# Sheet3.net
KiCad netlist of a schematic drawn in Altium Designer
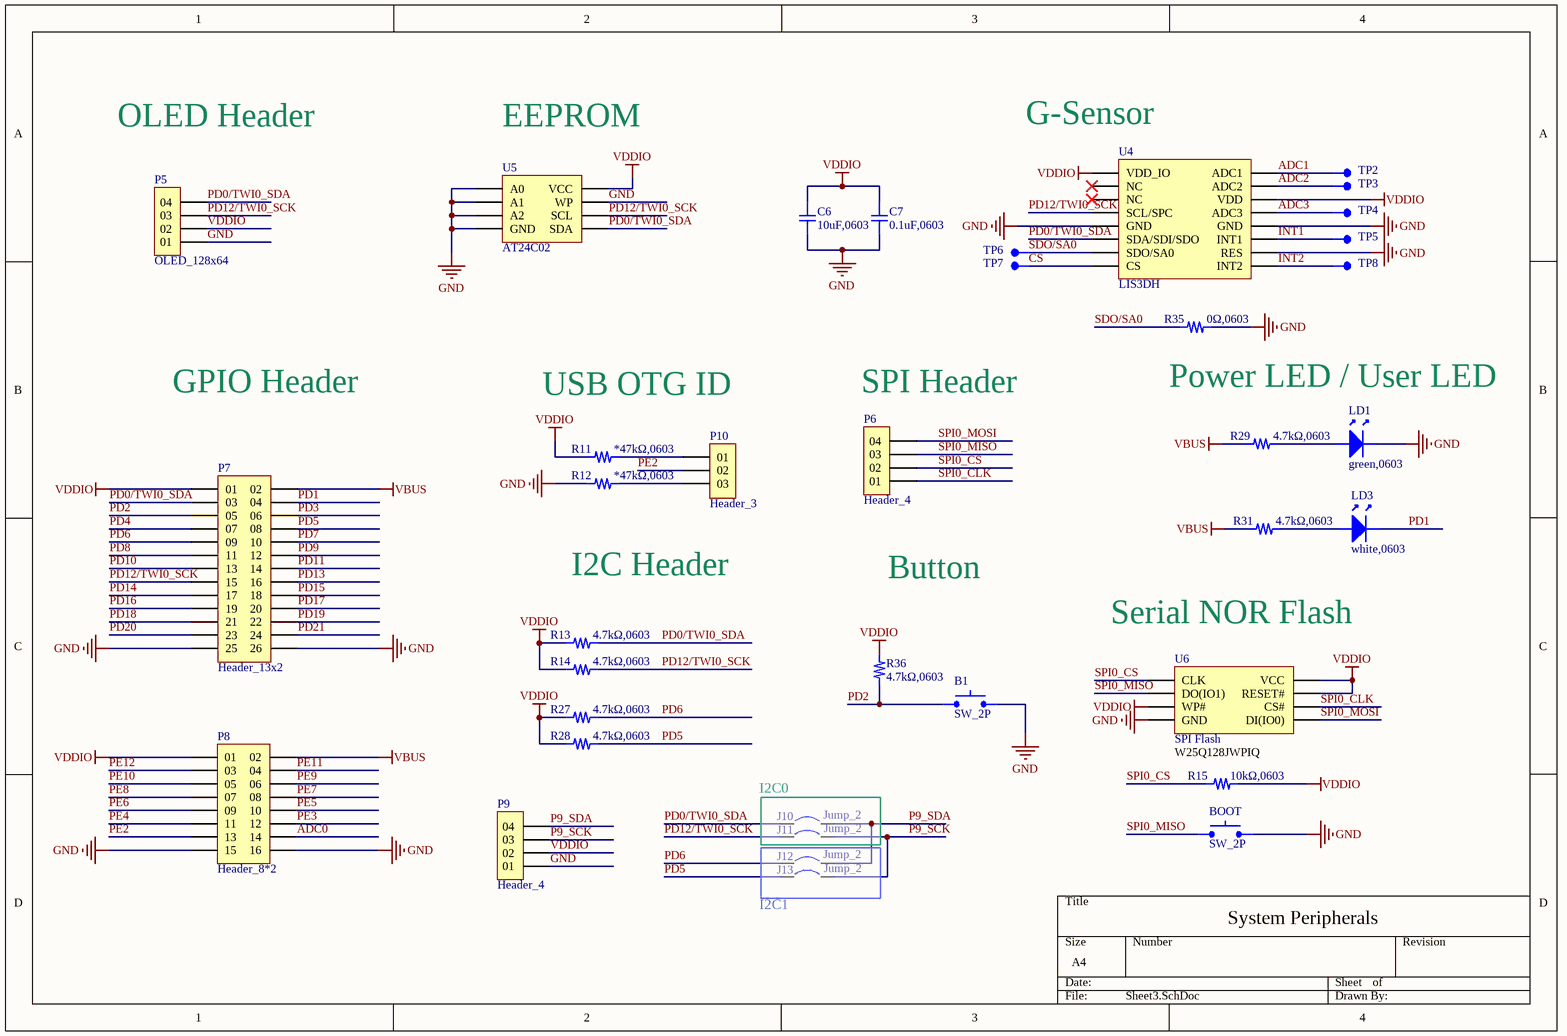
[diagram p0: Sheet3.SchDoc]

(export (version "E")
  (design (tool "Eeschema 10.0.6"))
  (components
    (comp (ref "B1") (value "SW_2P") (footprint "SW_2P_4") (libsource (lib "myLib1") (part "SW_2P")))
    (comp (ref "BOOT") (value "SW_2P") (footprint "SW_2P_4") (libsource (lib "myLib1") (part "SW_2P")))
    (comp (ref "C6") (value "10uF,0603") (footprint "C0603") (libsource (lib "myLib1") (part "Cap")))
    (comp (ref "C7") (value "0.1uF,0603") (footprint "C0603") (libsource (lib "myLib1") (part "Cap")))
    (comp (ref "J10") (value "Jump_2") (footprint "Jp_small") (libsource (lib "myLib1") (part "Jump_2")))
    (comp (ref "J11") (value "Jump_2") (footprint "Jp_small") (libsource (lib "myLib1") (part "Jump_2")))
    (comp (ref "J12") (value "Jump_2") (footprint "Jp_small") (libsource (lib "myLib1") (part "Jump_2")))
    (comp (ref "J13") (value "Jump_2") (footprint "Jp_small") (libsource (lib "myLib1") (part "Jump_2")))
    (comp (ref "LD1")
      (value "green,0603")
      (footprint "LED0603")
      (libsource (lib "myLib1") (part "Diode - LED"))
    )
    (comp (ref "LD3")
      (value "white,0603")
      (footprint "LED0603")
      (libsource (lib "myLib1") (part "Diode - LED"))
    )
    (comp (ref "P5")
      (value "OLED_128x64")
      (footprint "Header_4")
      (libsource (lib "myLib1") (part "Header_4"))
    )
    (comp (ref "P6")
      (value "Header_4")
      (footprint "HEADER_4_SMD")
      (libsource (lib "myLib1") (part "Header_4"))
    )
    (comp (ref "P7")
      (value "Header_13x2")
      (footprint "Header_13x2")
      (libsource (lib "myLib1") (part "Header_13x2"))
    )
    (comp (ref "P8")
      (value "Header_8*2")
      (footprint "Header_8*2")
      (libsource (lib "myLib1") (part "Header_8*2"))
    )
    (comp (ref "P9") (value "Header_4") (footprint "Header_4") (libsource (lib "myLib1") (part "Header_4")))
    (comp (ref "P10")
      (value "Header_3")
      (footprint "Header_3_2mm")
      (libsource (lib "myLib1") (part "Header_3"))
    )
    (comp (ref "R11") (value "*47kΩ,0603") (footprint "R0603") (libsource (lib "myLib1") (part "Res")))
    (comp (ref "R12") (value "*47kΩ,0603") (footprint "R0603") (libsource (lib "myLib1") (part "Res")))
    (comp (ref "R13") (value "4.7kΩ,0603") (footprint "R0603") (libsource (lib "myLib1") (part "Res")))
    (comp (ref "R14") (value "4.7kΩ,0603") (footprint "R0603") (libsource (lib "myLib1") (part "Res")))
    (comp (ref "R15") (value "10kΩ,0603") (footprint "R0603") (libsource (lib "myLib1") (part "Res")))
    (comp (ref "R27") (value "4.7kΩ,0603") (footprint "R0603") (libsource (lib "myLib1") (part "Res")))
    (comp (ref "R28") (value "4.7kΩ,0603") (footprint "R0603") (libsource (lib "myLib1") (part "Res")))
    (comp (ref "R29") (value "4.7kΩ,0603") (footprint "R0603") (libsource (lib "myLib1") (part "Res")))
    (comp (ref "R31") (value "4.7kΩ,0603") (footprint "R0603") (libsource (lib "myLib1") (part "Res")))
    (comp (ref "R35") (value "0Ω,0603") (footprint "R0603") (libsource (lib "myLib1") (part "Res")))
    (comp (ref "R36") (value "4.7kΩ,0603") (footprint "R0603") (libsource (lib "myLib1") (part "Res")))
    (comp (ref "TP2") (value "TP") (footprint "TP") (libsource (lib "myLib1") (part "TP")))
    (comp (ref "TP3") (value "TP") (footprint "TP") (libsource (lib "myLib1") (part "TP")))
    (comp (ref "TP4") (value "TP") (footprint "TP") (libsource (lib "myLib1") (part "TP")))
    (comp (ref "TP5") (value "TP") (footprint "TP") (libsource (lib "myLib1") (part "TP")))
    (comp (ref "TP6") (value "TP") (footprint "TP") (libsource (lib "myLib1") (part "TP")))
    (comp (ref "TP7") (value "TP") (footprint "TP") (libsource (lib "myLib1") (part "TP")))
    (comp (ref "TP8") (value "TP") (footprint "TP") (libsource (lib "myLib1") (part "TP")))
    (comp (ref "U4") (value "LIS3DH") (footprint "LGA-16") (libsource (lib "myLib1") (part "LIS3DH")))
    (comp (ref "U5") (value "AT24C02") (footprint "SOP8") (libsource (lib "myLib1") (part "AT24C02")))
    (comp (ref "U6") (value "SPI Flash") (footprint "WSON8") (libsource (lib "myLib1") (part "SPI Flash")))
  )
  (nets
    (net (code "1") (name "/ADC0") (class "Default")
      (node (ref "P8") (pin "14") (pinfunction "14_14") (pintype "passive"))
    )
    (net (code "2") (name "/ADC1") (class "Default")
      (node (ref "TP2") (pin "01") (pintype "passive"))
      (node (ref "U4") (pin "16") (pinfunction "ADC1_16") (pintype "passive"))
    )
    (net (code "3") (name "/ADC2") (class "Default")
      (node (ref "TP3") (pin "01") (pintype "passive"))
      (node (ref "U4") (pin "15") (pinfunction "ADC2_15") (pintype "passive"))
    )
    (net (code "4") (name "/ADC3") (class "Default")
      (node (ref "TP4") (pin "01") (pintype "passive"))
      (node (ref "U4") (pin "13") (pinfunction "ADC3_13") (pintype "passive"))
    )
    (net (code "5") (name "/CS") (class "Default")
      (node (ref "TP7") (pin "01") (pintype "passive"))
      (node (ref "U4") (pin "08") (pinfunction "CS_08") (pintype "passive"))
    )
    (net (code "6") (name "/INT1") (class "Default")
      (node (ref "TP5") (pin "01") (pintype "passive"))
      (node (ref "U4") (pin "11") (pinfunction "INT1_11") (pintype "passive"))
    )
    (net (code "7") (name "/INT2") (class "Default")
      (node (ref "TP8") (pin "01") (pintype "passive"))
      (node (ref "U4") (pin "09") (pinfunction "INT2_09") (pintype "passive"))
    )
    (net (code "8") (name "/P9_SCK") (class "Default")
      (node (ref "J11") (pin "02") (pinfunction "2_02") (pintype "passive"))
      (node (ref "J13") (pin "02") (pinfunction "2_02") (pintype "passive"))
      (node (ref "P9") (pin "03") (pinfunction "03_03") (pintype "passive"))
    )
    (net (code "9") (name "/P9_SDA") (class "Default")
      (node (ref "J10") (pin "02") (pinfunction "2_02") (pintype "passive"))
      (node (ref "J12") (pin "02") (pinfunction "2_02") (pintype "passive"))
      (node (ref "P9") (pin "04") (pinfunction "04_04") (pintype "passive"))
    )
    (net (code "10") (name "/PD0{slash}TWI0_SDA") (class "Default")
      (node (ref "J10") (pin "01") (pinfunction "1_01") (pintype "passive"))
      (node (ref "P5") (pin "04") (pinfunction "04_04") (pintype "passive"))
      (node (ref "P7") (pin "03") (pinfunction "03_03") (pintype "passive"))
      (node (ref "R13") (pin "02") (pintype "passive"))
      (node (ref "U4") (pin "06") (pinfunction "SDA/SDI/SDO_06") (pintype "passive"))
      (node (ref "U5") (pin "05") (pinfunction "SDA_05") (pintype "passive"))
    )
    (net (code "11") (name "/PD1") (class "Default")
      (node (ref "LD3") (pin "02") (pintype "passive"))
      (node (ref "P7") (pin "04") (pinfunction "04_04") (pintype "passive"))
    )
    (net (code "12") (name "/PD2") (class "Default")
      (node (ref "B1") (pin "01") (pintype "passive"))
      (node (ref "P7") (pin "05") (pinfunction "05_05") (pintype "passive"))
      (node (ref "R36") (pin "01") (pintype "passive"))
    )
    (net (code "13") (name "/PD3") (class "Default")
      (node (ref "P7") (pin "06") (pinfunction "06_06") (pintype "passive"))
    )
    (net (code "14") (name "/PD4") (class "Default")
      (node (ref "P7") (pin "07") (pinfunction "07_07") (pintype "passive"))
    )
    (net (code "15") (name "/PD5") (class "Default")
      (node (ref "J13") (pin "01") (pinfunction "1_01") (pintype "passive"))
      (node (ref "P7") (pin "08") (pinfunction "08_08") (pintype "passive"))
      (node (ref "R28") (pin "02") (pintype "passive"))
    )
    (net (code "16") (name "/PD6") (class "Default")
      (node (ref "J12") (pin "01") (pinfunction "1_01") (pintype "passive"))
      (node (ref "P7") (pin "09") (pinfunction "09_09") (pintype "passive"))
      (node (ref "R27") (pin "02") (pintype "passive"))
    )
    (net (code "17") (name "/PD7") (class "Default")
      (node (ref "P7") (pin "10") (pinfunction "10_10") (pintype "passive"))
    )
    (net (code "18") (name "/PD8") (class "Default")
      (node (ref "P7") (pin "11") (pinfunction "11_11") (pintype "passive"))
    )
    (net (code "19") (name "/PD9") (class "Default")
      (node (ref "P7") (pin "12") (pinfunction "12_12") (pintype "passive"))
    )
    (net (code "20") (name "/PD10") (class "Default")
      (node (ref "P7") (pin "13") (pinfunction "13_13") (pintype "passive"))
    )
    (net (code "21") (name "/PD11") (class "Default")
      (node (ref "P7") (pin "14") (pinfunction "14_14") (pintype "passive"))
    )
    (net (code "22") (name "/PD12{slash}TWI0_SCK") (class "Default")
      (node (ref "J11") (pin "01") (pinfunction "1_01") (pintype "passive"))
      (node (ref "P5") (pin "03") (pinfunction "03_03") (pintype "passive"))
      (node (ref "P7") (pin "15") (pinfunction "15_15") (pintype "passive"))
      (node (ref "R14") (pin "02") (pintype "passive"))
      (node (ref "U4") (pin "04") (pinfunction "SCL/SPC_04") (pintype "passive"))
      (node (ref "U5") (pin "06") (pinfunction "SCL_06") (pintype "passive"))
    )
    (net (code "23") (name "/PD13") (class "Default")
      (node (ref "P7") (pin "16") (pinfunction "16_16") (pintype "passive"))
    )
    (net (code "24") (name "/PD14") (class "Default")
      (node (ref "P7") (pin "17") (pinfunction "17_17") (pintype "passive"))
    )
    (net (code "25") (name "/PD15") (class "Default")
      (node (ref "P7") (pin "18") (pinfunction "18_18") (pintype "passive"))
    )
    (net (code "26") (name "/PD16") (class "Default")
      (node (ref "P7") (pin "19") (pinfunction "19_19") (pintype "passive"))
    )
    (net (code "27") (name "/PD17") (class "Default")
      (node (ref "P7") (pin "20") (pinfunction "20_20") (pintype "passive"))
    )
    (net (code "28") (name "/PD18") (class "Default")
      (node (ref "P7") (pin "21") (pinfunction "21_21") (pintype "passive"))
    )
    (net (code "29") (name "/PD19") (class "Default")
      (node (ref "P7") (pin "22") (pinfunction "22_22") (pintype "passive"))
    )
    (net (code "30") (name "/PD20") (class "Default")
      (node (ref "P7") (pin "23") (pinfunction "23_23") (pintype "passive"))
    )
    (net (code "31") (name "/PD21") (class "Default")
      (node (ref "P7") (pin "24") (pinfunction "24_24") (pintype "passive"))
    )
    (net (code "32") (name "/PE2") (class "Default")
      (node (ref "P10") (pin "02") (pinfunction "02_02") (pintype "passive"))
      (node (ref "P8") (pin "13") (pinfunction "13_13") (pintype "passive"))
    )
    (net (code "33") (name "/PE3") (class "Default")
      (node (ref "P8") (pin "12") (pinfunction "12_12") (pintype "passive"))
    )
    (net (code "34") (name "/PE4") (class "Default")
      (node (ref "P8") (pin "11") (pinfunction "11_11") (pintype "passive"))
    )
    (net (code "35") (name "/PE5") (class "Default")
      (node (ref "P8") (pin "10") (pinfunction "10_10") (pintype "passive"))
    )
    (net (code "36") (name "/PE6") (class "Default")
      (node (ref "P8") (pin "09") (pinfunction "09_09") (pintype "passive"))
    )
    (net (code "37") (name "/PE7") (class "Default")
      (node (ref "P8") (pin "08") (pinfunction "08_08") (pintype "passive"))
    )
    (net (code "38") (name "/PE8") (class "Default")
      (node (ref "P8") (pin "07") (pinfunction "07_07") (pintype "passive"))
    )
    (net (code "39") (name "/PE9") (class "Default")
      (node (ref "P8") (pin "06") (pinfunction "06_06") (pintype "passive"))
    )
    (net (code "40") (name "/PE10") (class "Default")
      (node (ref "P8") (pin "05") (pinfunction "05_05") (pintype "passive"))
    )
    (net (code "41") (name "/PE11") (class "Default")
      (node (ref "P8") (pin "04") (pinfunction "04_04") (pintype "passive"))
    )
    (net (code "42") (name "/PE12") (class "Default")
      (node (ref "P8") (pin "03") (pinfunction "03_03") (pintype "passive"))
    )
    (net (code "43") (name "/SDO{slash}SA0") (class "Default")
      (node (ref "R35") (pin "01") (pintype "passive"))
      (node (ref "TP6") (pin "01") (pintype "passive"))
      (node (ref "U4") (pin "07") (pinfunction "SDO/SA0_07") (pintype "passive"))
    )
    (net (code "44") (name "/SPI0_CLK") (class "Default")
      (node (ref "P6") (pin "01") (pinfunction "01_01") (pintype "passive"))
      (node (ref "U6") (pin "01") (pinfunction "CS#_01") (pintype "passive"))
    )
    (net (code "45") (name "/SPI0_CS") (class "Default")
      (node (ref "P6") (pin "02") (pinfunction "02_02") (pintype "passive"))
      (node (ref "R15") (pin "01") (pintype "passive"))
      (node (ref "U6") (pin "06") (pinfunction "CLK_06") (pintype "passive"))
    )
    (net (code "46") (name "/SPI0_MISO") (class "Default")
      (node (ref "BOOT") (pin "01") (pintype "passive"))
      (node (ref "P6") (pin "03") (pinfunction "03_03") (pintype "passive"))
      (node (ref "U6") (pin "02") (pinfunction "DO(IO1)_02") (pintype "passive"))
    )
    (net (code "47") (name "/SPI0_MOSI") (class "Default")
      (node (ref "P6") (pin "04") (pinfunction "04_04") (pintype "passive"))
      (node (ref "U6") (pin "05") (pinfunction "DI(IO0)_05") (pintype "passive"))
    )
    (net (code "48") (name "GND") (class "Default")
      (node (ref "B1") (pin "02") (pintype "passive"))
      (node (ref "BOOT") (pin "02") (pintype "passive"))
      (node (ref "C6") (pin "01") (pintype "passive"))
      (node (ref "C7") (pin "01") (pintype "passive"))
      (node (ref "LD1") (pin "02") (pintype "passive"))
      (node (ref "P5") (pin "01") (pinfunction "01_01") (pintype "passive"))
      (node (ref "P7") (pin "25") (pinfunction "25_25") (pintype "passive"))
      (node (ref "P7") (pin "26") (pinfunction "26_26") (pintype "passive"))
      (node (ref "P8") (pin "15") (pinfunction "15_15") (pintype "passive"))
      (node (ref "P8") (pin "16") (pinfunction "16_16") (pintype "passive"))
      (node (ref "P9") (pin "01") (pinfunction "01_01") (pintype "passive"))
      (node (ref "R12") (pin "01") (pintype "passive"))
      (node (ref "R35") (pin "02") (pintype "passive"))
      (node (ref "U4") (pin "05") (pinfunction "GND_05") (pintype "passive"))
      (node (ref "U4") (pin "10") (pinfunction "RES_10") (pintype "passive"))
      (node (ref "U4") (pin "12") (pinfunction "GND_12") (pintype "passive"))
      (node (ref "U5") (pin "01") (pinfunction "A0_01") (pintype "passive"))
      (node (ref "U5") (pin "02") (pinfunction "A1_02") (pintype "passive"))
      (node (ref "U5") (pin "03") (pinfunction "A2_03") (pintype "passive"))
      (node (ref "U5") (pin "04") (pinfunction "GND_04") (pintype "passive"))
      (node (ref "U5") (pin "07") (pinfunction "WP_07") (pintype "passive"))
      (node (ref "U6") (pin "04") (pinfunction "GND_04") (pintype "passive"))
    )
    (net (code "49") (name "Net-(LD1-Pad01)") (class "Default")
      (node (ref "LD1") (pin "01") (pintype "passive"))
      (node (ref "R29") (pin "02") (pintype "passive"))
    )
    (net (code "50") (name "Net-(LD3-Pad01)") (class "Default")
      (node (ref "LD3") (pin "01") (pintype "passive"))
      (node (ref "R31") (pin "02") (pintype "passive"))
    )
    (net (code "51") (name "Net-(P10-Pad01)") (class "Default")
      (node (ref "P10") (pin "01") (pinfunction "01_01") (pintype "passive"))
      (node (ref "R11") (pin "02") (pintype "passive"))
    )
    (net (code "52") (name "Net-(P10-Pad03)") (class "Default")
      (node (ref "P10") (pin "03") (pinfunction "03_03") (pintype "passive"))
      (node (ref "R12") (pin "02") (pintype "passive"))
    )
    (net (code "53") (name "VBUS") (class "Default")
      (node (ref "P7") (pin "02") (pinfunction "02_02") (pintype "passive"))
      (node (ref "P8") (pin "02") (pinfunction "02_02") (pintype "passive"))
      (node (ref "R29") (pin "01") (pintype "passive"))
      (node (ref "R31") (pin "01") (pintype "passive"))
    )
    (net (code "54") (name "VDDIO") (class "Default")
      (node (ref "C6") (pin "02") (pintype "passive"))
      (node (ref "C7") (pin "02") (pintype "passive"))
      (node (ref "P5") (pin "02") (pinfunction "02_02") (pintype "passive"))
      (node (ref "P7") (pin "01") (pinfunction "01_01") (pintype "passive"))
      (node (ref "P8") (pin "01") (pinfunction "01_01") (pintype "passive"))
      (node (ref "P9") (pin "02") (pinfunction "02_02") (pintype "passive"))
      (node (ref "R11") (pin "01") (pintype "passive"))
      (node (ref "R13") (pin "01") (pintype "passive"))
      (node (ref "R14") (pin "01") (pintype "passive"))
      (node (ref "R15") (pin "02") (pintype "passive"))
      (node (ref "R27") (pin "01") (pintype "passive"))
      (node (ref "R28") (pin "01") (pintype "passive"))
      (node (ref "R36") (pin "02") (pintype "passive"))
      (node (ref "U4") (pin "01") (pinfunction "VDD_IO_01") (pintype "passive"))
      (node (ref "U4") (pin "14") (pinfunction "VDD_14") (pintype "passive"))
      (node (ref "U5") (pin "08") (pinfunction "VCC_08") (pintype "passive"))
      (node (ref "U6") (pin "03") (pinfunction "WP#_03") (pintype "passive"))
      (node (ref "U6") (pin "07") (pinfunction "RESET#_07") (pintype "passive"))
      (node (ref "U6") (pin "08") (pinfunction "VCC_08") (pintype "passive"))
    )
    (net (code "55") (name "unconnected-(U4-NC-Pad02)") (class "Default")
      (node (ref "U4") (pin "02") (pinfunction "NC_02") (pintype "passive+no_connect"))
    )
    (net (code "56") (name "unconnected-(U4-NC-Pad03)") (class "Default")
      (node (ref "U4") (pin "03") (pinfunction "NC_03") (pintype "passive+no_connect"))
    )
  )
)
